# enkodery.net
KiCad netlist of a schematic drawn in EAGLE
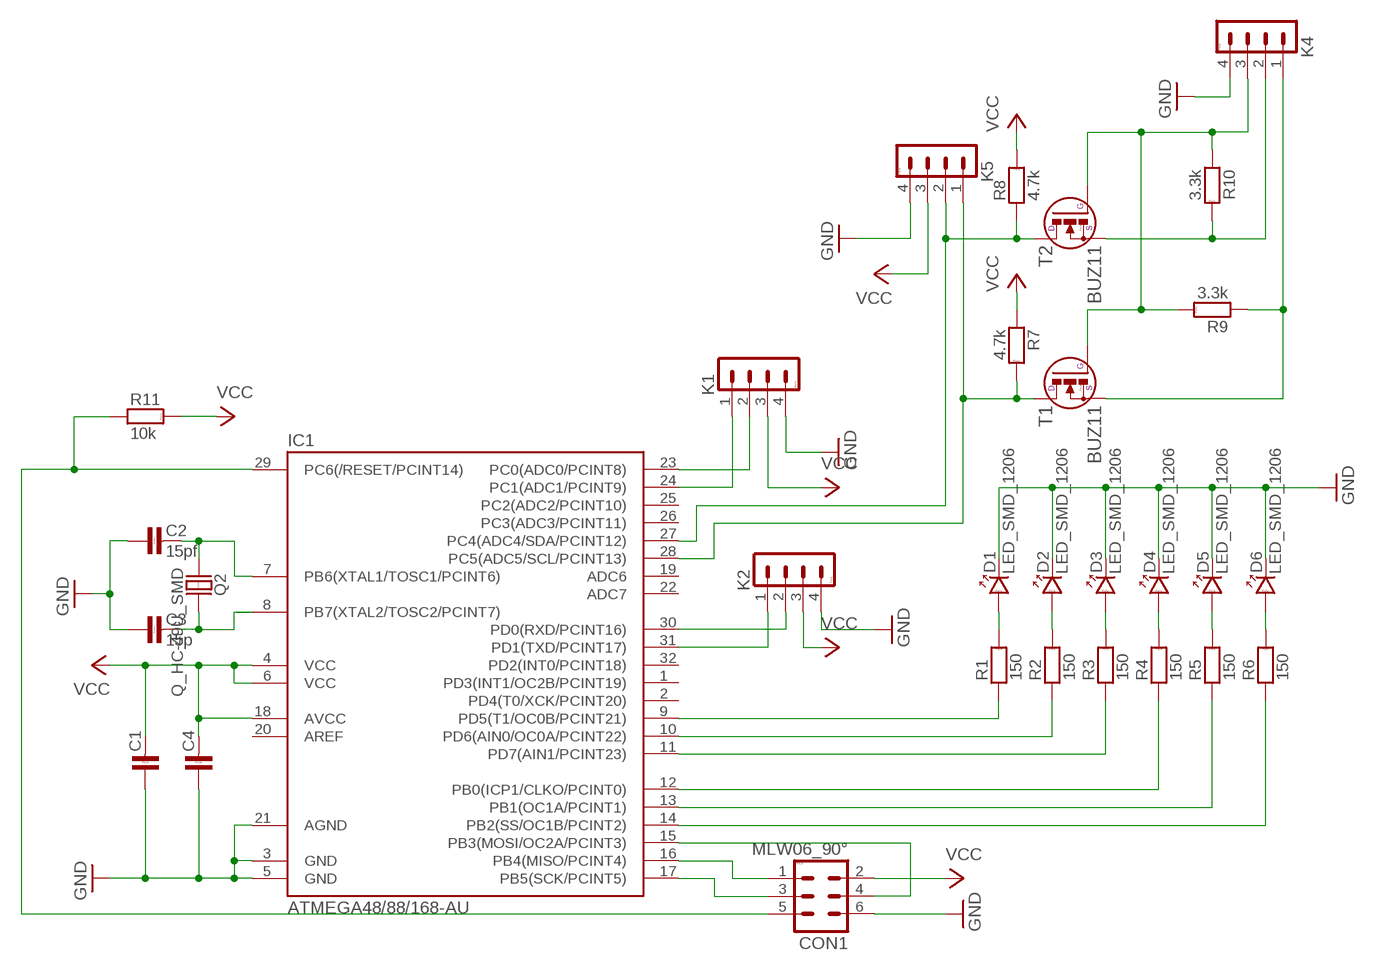
[diagram p0: schematic, sheet 1]

(export (version "E")
  (design (tool "Eeschema 10.0.6"))
  (components
    (comp (ref "C1")
      (value "C-KERAMIK_SMD_1206")
      (footprint "eagle-import:1206")
      (libsource (lib "eagle-import") (part "C-KERAMIK_SMD_1206"))
    )
    (comp (ref "C2")
      (value "15pf")
      (footprint "eagle-import:1206")
      (libsource (lib "eagle-import") (part "C-KERAMIK_SMD_1206"))
    )
    (comp (ref "C3")
      (value "15p")
      (footprint "eagle-import:1206")
      (libsource (lib "eagle-import") (part "C-KERAMIK_SMD_1206"))
    )
    (comp (ref "C4")
      (value "C-KERAMIK_SMD_1206")
      (footprint "eagle-import:1206")
      (libsource (lib "eagle-import") (part "C-KERAMIK_SMD_1206"))
    )
    (comp (ref "CON1")
      (value "MLW06_90°")
      (footprint "eagle-import:MLW06A")
      (libsource (lib "eagle-import") (part "MLW06_90°"))
    )
    (comp (ref "D1")
      (value "LED_SMD_1206")
      (footprint "eagle-import:P1206")
      (libsource (lib "eagle-import") (part "LED_SMD_1206"))
    )
    (comp (ref "D2")
      (value "LED_SMD_1206")
      (footprint "eagle-import:P1206")
      (libsource (lib "eagle-import") (part "LED_SMD_1206"))
    )
    (comp (ref "D3")
      (value "LED_SMD_1206")
      (footprint "eagle-import:P1206")
      (libsource (lib "eagle-import") (part "LED_SMD_1206"))
    )
    (comp (ref "D4")
      (value "LED_SMD_1206")
      (footprint "eagle-import:P1206")
      (libsource (lib "eagle-import") (part "LED_SMD_1206"))
    )
    (comp (ref "D5")
      (value "LED_SMD_1206")
      (footprint "eagle-import:P1206")
      (libsource (lib "eagle-import") (part "LED_SMD_1206"))
    )
    (comp (ref "D6")
      (value "LED_SMD_1206")
      (footprint "eagle-import:P1206")
      (libsource (lib "eagle-import") (part "LED_SMD_1206"))
    )
    (comp (ref "IC1")
      (value "ATMEGA48/88/168-AU")
      (footprint "eagle-import:TQFP32-08")
      (libsource (lib "eagle-import") (part "ATMEGA48/88/168-AU"))
    )
    (comp (ref "K1")
      (value "PSH02-04W")
      (footprint "eagle-import:PSH02-04W")
      (libsource (lib "eagle-import") (part "PSH02-04W"))
    )
    (comp (ref "K2")
      (value "PSH02-04W")
      (footprint "eagle-import:PSH02-04W")
      (libsource (lib "eagle-import") (part "PSH02-04W"))
    )
    (comp (ref "K4")
      (value "PSH02-04W")
      (footprint "eagle-import:PSH02-04W")
      (libsource (lib "eagle-import") (part "PSH02-04W"))
    )
    (comp (ref "K5")
      (value "PSH02-04W")
      (footprint "eagle-import:PSH02-04W")
      (libsource (lib "eagle-import") (part "PSH02-04W"))
    )
    (comp (ref "Q2")
      (value "Q_HC-49U_SMD")
      (footprint "eagle-import:HC-49US")
      (libsource (lib "eagle-import") (part "Q_HC-49U_SMD"))
    )
    (comp (ref "R1")
      (value "150")
      (footprint "eagle-import:1206")
      (libsource (lib "eagle-import") (part "R_SMD_1206"))
    )
    (comp (ref "R2")
      (value "150")
      (footprint "eagle-import:1206")
      (libsource (lib "eagle-import") (part "R_SMD_1206"))
    )
    (comp (ref "R3")
      (value "150")
      (footprint "eagle-import:1206")
      (libsource (lib "eagle-import") (part "R_SMD_1206"))
    )
    (comp (ref "R4")
      (value "150")
      (footprint "eagle-import:1206")
      (libsource (lib "eagle-import") (part "R_SMD_1206"))
    )
    (comp (ref "R5")
      (value "150")
      (footprint "eagle-import:1206")
      (libsource (lib "eagle-import") (part "R_SMD_1206"))
    )
    (comp (ref "R6")
      (value "150")
      (footprint "eagle-import:1206")
      (libsource (lib "eagle-import") (part "R_SMD_1206"))
    )
    (comp (ref "R7")
      (value "4.7k")
      (footprint "eagle-import:1206")
      (libsource (lib "eagle-import") (part "R_SMD_1206"))
    )
    (comp (ref "R8")
      (value "4.7k")
      (footprint "eagle-import:1206")
      (libsource (lib "eagle-import") (part "R_SMD_1206"))
    )
    (comp (ref "R9")
      (value "3.3k")
      (footprint "eagle-import:1206")
      (libsource (lib "eagle-import") (part "R_SMD_1206"))
    )
    (comp (ref "R10")
      (value "3.3k")
      (footprint "eagle-import:1206")
      (libsource (lib "eagle-import") (part "R_SMD_1206"))
    )
    (comp (ref "R11")
      (value "10k")
      (footprint "eagle-import:1206")
      (libsource (lib "eagle-import") (part "R_SMD_1206"))
    )
    (comp (ref "T1")
      (value "BUZ11")
      (footprint "eagle-import:SOT23")
      (libsource (lib "eagle-import") (part "BUZ11"))
    )
    (comp (ref "T2")
      (value "BUZ11")
      (footprint "eagle-import:SOT23")
      (libsource (lib "eagle-import") (part "BUZ11"))
    )
  )
  (nets
    (net (code "1") (name "GND") (class "Default")
      (node (ref "C1") (pin "1") (pinfunction "1_1") (pintype "passive"))
      (node (ref "C2") (pin "1") (pinfunction "1_1") (pintype "passive"))
      (node (ref "C3") (pin "1") (pinfunction "1_1") (pintype "passive"))
      (node (ref "C4") (pin "1") (pinfunction "1_1") (pintype "passive"))
      (node (ref "CON1") (pin "6") (pinfunction "6_6") (pintype "passive"))
      (node (ref "D1") (pin "K") (pinfunction "K_K") (pintype "passive"))
      (node (ref "D2") (pin "K") (pinfunction "K_K") (pintype "passive"))
      (node (ref "D3") (pin "K") (pinfunction "K_K") (pintype "passive"))
      (node (ref "D4") (pin "K") (pinfunction "K_K") (pintype "passive"))
      (node (ref "D5") (pin "K") (pinfunction "K_K") (pintype "passive"))
      (node (ref "D6") (pin "K") (pinfunction "K_K") (pintype "passive"))
      (node (ref "IC1") (pin "21") (pinfunction "AGND_21") (pintype "power_in"))
      (node (ref "IC1") (pin "3") (pinfunction "GND_3") (pintype "power_in"))
      (node (ref "IC1") (pin "5") (pinfunction "GND_5") (pintype "power_in"))
      (node (ref "K1") (pin "4") (pinfunction "4_4") (pintype "passive"))
      (node (ref "K2") (pin "4") (pinfunction "4_4") (pintype "passive"))
      (node (ref "K4") (pin "4") (pinfunction "4_4") (pintype "passive"))
      (node (ref "K5") (pin "4") (pinfunction "4_4") (pintype "passive"))
    )
    (net (code "2") (name "Net-(D1-PadA)") (class "Default")
      (node (ref "D1") (pin "A") (pinfunction "A_A") (pintype "passive"))
      (node (ref "R1") (pin "2") (pinfunction "2_2") (pintype "passive"))
    )
    (net (code "3") (name "Net-(D2-PadA)") (class "Default")
      (node (ref "D2") (pin "A") (pinfunction "A_A") (pintype "passive"))
      (node (ref "R2") (pin "2") (pinfunction "2_2") (pintype "passive"))
    )
    (net (code "4") (name "Net-(D3-PadA)") (class "Default")
      (node (ref "D3") (pin "A") (pinfunction "A_A") (pintype "passive"))
      (node (ref "R3") (pin "2") (pinfunction "2_2") (pintype "passive"))
    )
    (net (code "5") (name "Net-(D4-PadA)") (class "Default")
      (node (ref "D4") (pin "A") (pinfunction "A_A") (pintype "passive"))
      (node (ref "R4") (pin "2") (pinfunction "2_2") (pintype "passive"))
    )
    (net (code "6") (name "Net-(D5-PadA)") (class "Default")
      (node (ref "D5") (pin "A") (pinfunction "A_A") (pintype "passive"))
      (node (ref "R5") (pin "2") (pinfunction "2_2") (pintype "passive"))
    )
    (net (code "7") (name "Net-(D6-PadA)") (class "Default")
      (node (ref "D6") (pin "A") (pinfunction "A_A") (pintype "passive"))
      (node (ref "R6") (pin "2") (pinfunction "2_2") (pintype "passive"))
    )
    (net (code "8") (name "Net-(IC1-PB0(ICP1{slash}CLKO{slash}PCINT0))") (class "Default")
      (node (ref "IC1") (pin "12") (pinfunction "PB0(ICP1/CLKO/PCINT0)_12") (pintype "bidirectional"))
      (node (ref "R4") (pin "1") (pinfunction "1_1") (pintype "passive"))
    )
    (net (code "9") (name "Net-(IC1-PB1(OC1A{slash}PCINT1))") (class "Default")
      (node (ref "IC1") (pin "13") (pinfunction "PB1(OC1A/PCINT1)_13") (pintype "bidirectional"))
      (node (ref "R5") (pin "1") (pinfunction "1_1") (pintype "passive"))
    )
    (net (code "10") (name "Net-(IC1-PB2(SS{slash}OC1B{slash}PCINT2))") (class "Default")
      (node (ref "IC1") (pin "14") (pinfunction "PB2(SS/OC1B/PCINT2)_14") (pintype "bidirectional"))
      (node (ref "R6") (pin "1") (pinfunction "1_1") (pintype "passive"))
    )
    (net (code "11") (name "Net-(IC1-PB3(MOSI{slash}OC2A{slash}PCINT3))") (class "Default")
      (node (ref "CON1") (pin "4") (pinfunction "4_4") (pintype "passive"))
      (node (ref "IC1") (pin "15") (pinfunction "PB3(MOSI/OC2A/PCINT3)_15") (pintype "bidirectional"))
    )
    (net (code "12") (name "Net-(IC1-PB4(MISO{slash}PCINT4))") (class "Default")
      (node (ref "CON1") (pin "1") (pinfunction "1_1") (pintype "passive"))
      (node (ref "IC1") (pin "16") (pinfunction "PB4(MISO/PCINT4)_16") (pintype "bidirectional"))
    )
    (net (code "13") (name "Net-(IC1-PB5(SCK{slash}PCINT5))") (class "Default")
      (node (ref "CON1") (pin "3") (pinfunction "3_3") (pintype "passive"))
      (node (ref "IC1") (pin "17") (pinfunction "PB5(SCK/PCINT5)_17") (pintype "bidirectional"))
    )
    (net (code "14") (name "Net-(IC1-PB6(XTAL1{slash}TOSC1{slash}PCINT6))") (class "Default")
      (node (ref "C2") (pin "2") (pinfunction "2_2") (pintype "passive"))
      (node (ref "IC1") (pin "7") (pinfunction "PB6(XTAL1/TOSC1/PCINT6)_7") (pintype "bidirectional"))
      (node (ref "Q2") (pin "1") (pinfunction "1_1") (pintype "passive"))
    )
    (net (code "15") (name "Net-(IC1-PB7(XTAL2{slash}TOSC2{slash}PCINT7))") (class "Default")
      (node (ref "C3") (pin "2") (pinfunction "2_2") (pintype "passive"))
      (node (ref "IC1") (pin "8") (pinfunction "PB7(XTAL2/TOSC2/PCINT7)_8") (pintype "bidirectional"))
      (node (ref "Q2") (pin "2") (pinfunction "2_2") (pintype "passive"))
    )
    (net (code "16") (name "Net-(IC1-PC0(ADC0{slash}PCINT8))") (class "Default")
      (node (ref "IC1") (pin "23") (pinfunction "PC0(ADC0/PCINT8)_23") (pintype "bidirectional"))
      (node (ref "K1") (pin "2") (pinfunction "2_2") (pintype "passive"))
    )
    (net (code "17") (name "Net-(IC1-PC1(ADC1{slash}PCINT9))") (class "Default")
      (node (ref "IC1") (pin "24") (pinfunction "PC1(ADC1/PCINT9)_24") (pintype "bidirectional"))
      (node (ref "K1") (pin "1") (pinfunction "1_1") (pintype "passive"))
    )
    (net (code "18") (name "Net-(IC1-PC4(ADC4{slash}SDA{slash}PCINT12))") (class "Default")
      (node (ref "IC1") (pin "27") (pinfunction "PC4(ADC4/SDA/PCINT12)_27") (pintype "bidirectional"))
      (node (ref "K5") (pin "2") (pinfunction "2_2") (pintype "passive"))
      (node (ref "R8") (pin "1") (pinfunction "1_1") (pintype "passive"))
      (node (ref "T2") (pin "3") (pinfunction "D_3") (pintype "passive"))
    )
    (net (code "19") (name "Net-(IC1-PC5(ADC5{slash}SCL{slash}PCINT13))") (class "Default")
      (node (ref "IC1") (pin "28") (pinfunction "PC5(ADC5/SCL/PCINT13)_28") (pintype "bidirectional"))
      (node (ref "K5") (pin "1") (pinfunction "1_1") (pintype "passive"))
      (node (ref "R7") (pin "2") (pinfunction "2_2") (pintype "passive"))
      (node (ref "T1") (pin "3") (pinfunction "D_3") (pintype "passive"))
    )
    (net (code "20") (name "Net-(IC1-PC6({slash}RESET{slash}PCINT14))") (class "Default")
      (node (ref "CON1") (pin "5") (pinfunction "5_5") (pintype "passive"))
      (node (ref "IC1") (pin "29") (pinfunction "PC6(/RESET/PCINT14)_29") (pintype "bidirectional"))
      (node (ref "R11") (pin "1") (pinfunction "1_1") (pintype "passive"))
    )
    (net (code "21") (name "Net-(IC1-PD0(RXD{slash}PCINT16))") (class "Default")
      (node (ref "IC1") (pin "30") (pinfunction "PD0(RXD/PCINT16)_30") (pintype "bidirectional"))
      (node (ref "K2") (pin "2") (pinfunction "2_2") (pintype "passive"))
    )
    (net (code "22") (name "Net-(IC1-PD1(TXD{slash}PCINT17))") (class "Default")
      (node (ref "IC1") (pin "31") (pinfunction "PD1(TXD/PCINT17)_31") (pintype "bidirectional"))
      (node (ref "K2") (pin "1") (pinfunction "1_1") (pintype "passive"))
    )
    (net (code "23") (name "Net-(IC1-PD5(T1{slash}OC0B{slash}PCINT21))") (class "Default")
      (node (ref "IC1") (pin "9") (pinfunction "PD5(T1/OC0B/PCINT21)_9") (pintype "bidirectional"))
      (node (ref "R1") (pin "1") (pinfunction "1_1") (pintype "passive"))
    )
    (net (code "24") (name "Net-(IC1-PD6(AIN0{slash}OC0A{slash}PCINT22))") (class "Default")
      (node (ref "IC1") (pin "10") (pinfunction "PD6(AIN0/OC0A/PCINT22)_10") (pintype "bidirectional"))
      (node (ref "R2") (pin "1") (pinfunction "1_1") (pintype "passive"))
    )
    (net (code "25") (name "Net-(IC1-PD7(AIN1{slash}PCINT23))") (class "Default")
      (node (ref "IC1") (pin "11") (pinfunction "PD7(AIN1/PCINT23)_11") (pintype "bidirectional"))
      (node (ref "R3") (pin "1") (pinfunction "1_1") (pintype "passive"))
    )
    (net (code "26") (name "Net-(T1-G)") (class "Default")
      (node (ref "K4") (pin "3") (pinfunction "3_3") (pintype "passive"))
      (node (ref "R10") (pin "1") (pinfunction "1_1") (pintype "passive"))
      (node (ref "R9") (pin "2") (pinfunction "2_2") (pintype "passive"))
      (node (ref "T1") (pin "1") (pinfunction "G_1") (pintype "passive"))
      (node (ref "T2") (pin "1") (pinfunction "G_1") (pintype "passive"))
    )
    (net (code "27") (name "Net-(T1-S)") (class "Default")
      (node (ref "K4") (pin "1") (pinfunction "1_1") (pintype "passive"))
      (node (ref "R9") (pin "1") (pinfunction "1_1") (pintype "passive"))
      (node (ref "T1") (pin "2") (pinfunction "S_2") (pintype "passive"))
    )
    (net (code "28") (name "Net-(T2-S)") (class "Default")
      (node (ref "K4") (pin "2") (pinfunction "2_2") (pintype "passive"))
      (node (ref "R10") (pin "2") (pinfunction "2_2") (pintype "passive"))
      (node (ref "T2") (pin "2") (pinfunction "S_2") (pintype "passive"))
    )
    (net (code "29") (name "VCC") (class "Default")
      (node (ref "C1") (pin "2") (pinfunction "2_2") (pintype "passive"))
      (node (ref "C4") (pin "2") (pinfunction "2_2") (pintype "passive"))
      (node (ref "CON1") (pin "2") (pinfunction "2_2") (pintype "passive"))
      (node (ref "IC1") (pin "18") (pinfunction "AVCC_18") (pintype "passive"))
      (node (ref "IC1") (pin "4") (pinfunction "VCC_4") (pintype "power_in"))
      (node (ref "IC1") (pin "6") (pinfunction "VCC_6") (pintype "power_in"))
      (node (ref "K1") (pin "3") (pinfunction "3_3") (pintype "passive"))
      (node (ref "K2") (pin "3") (pinfunction "3_3") (pintype "passive"))
      (node (ref "K5") (pin "3") (pinfunction "3_3") (pintype "passive"))
      (node (ref "R11") (pin "2") (pinfunction "2_2") (pintype "passive"))
      (node (ref "R7") (pin "1") (pinfunction "1_1") (pintype "passive"))
      (node (ref "R8") (pin "2") (pinfunction "2_2") (pintype "passive"))
    )
    (net (code "30") (name "unconnected-(IC1-ADC6-Pad19)") (class "Default")
      (node (ref "IC1") (pin "19") (pinfunction "ADC6_19") (pintype "passive"))
    )
    (net (code "31") (name "unconnected-(IC1-ADC7-Pad22)") (class "Default")
      (node (ref "IC1") (pin "22") (pinfunction "ADC7_22") (pintype "passive"))
    )
    (net (code "32") (name "unconnected-(IC1-AREF-Pad20)") (class "Default")
      (node (ref "IC1") (pin "20") (pinfunction "AREF_20") (pintype "passive"))
    )
    (net (code "33") (name "unconnected-(IC1-PC2(ADC2{slash}PCINT10)-Pad25)") (class "Default")
      (node (ref "IC1") (pin "25") (pinfunction "PC2(ADC2/PCINT10)_25") (pintype "bidirectional"))
    )
    (net (code "34") (name "unconnected-(IC1-PC3(ADC3{slash}PCINT11)-Pad26)") (class "Default")
      (node (ref "IC1") (pin "26") (pinfunction "PC3(ADC3/PCINT11)_26") (pintype "bidirectional"))
    )
    (net (code "35") (name "unconnected-(IC1-PD2(INT0{slash}PCINT18)-Pad32)") (class "Default")
      (node (ref "IC1") (pin "32") (pinfunction "PD2(INT0/PCINT18)_32") (pintype "bidirectional"))
    )
    (net (code "36") (name "unconnected-(IC1-PD3(INT1{slash}OC2B{slash}PCINT19)-Pad1)") (class "Default")
      (node (ref "IC1") (pin "1") (pinfunction "PD3(INT1/OC2B/PCINT19)_1") (pintype "bidirectional"))
    )
    (net (code "37") (name "unconnected-(IC1-PD4(T0{slash}XCK{slash}PCINT20)-Pad2)") (class "Default")
      (node (ref "IC1") (pin "2") (pinfunction "PD4(T0/XCK/PCINT20)_2") (pintype "bidirectional"))
    )
  )
)
